# LF_v5_SensorBoard.net
KiCad netlist of a schematic drawn in Altium Designer
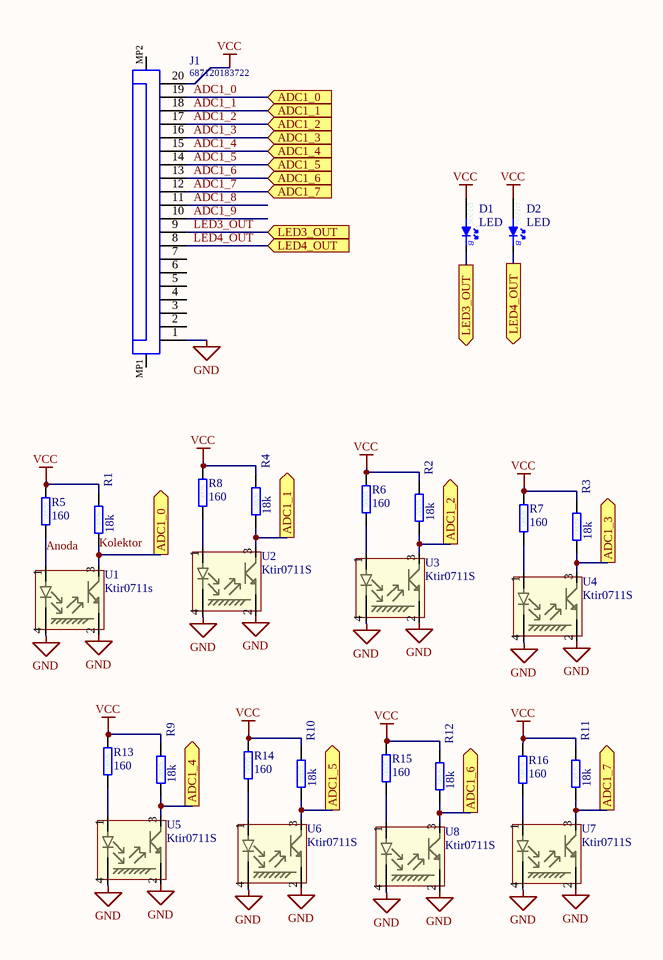
[diagram p0: LF_v5_SensorBoard.SchDoc]

(export (version "E")
  (design (tool "Eeschema 10.0.6"))
  (components
    (comp (ref "D1")
      (value "LED")
      (footprint "D1206_2")
      (description "Dioda LED Niebieska  120°   20mA   14-22 mCd")
      (libsource (lib "DIODY_LED_SMD__00001") (part "LL-S150BC-B4-1B  D1206"))
    )
    (comp (ref "D2")
      (value "LED")
      (footprint "D1206_2")
      (description "Dioda LED Niebieska  120°   20mA   14-22 mCd")
      (libsource (lib "DIODY_LED_SMD__00001") (part "LL-S150BC-B4-1B  D1206"))
    )
    (comp (ref "J1")
      (value "687120183722")
      (footprint "687120183722")
      (description "SMT ZIF Connectors Low Profile WR-FPC, Horizontal, Bottom Contact, pitch 0.5 mm, 20 pins")
      (fields (field (name "MANUFACTURER") "Wurth Elektronik") (field (name "PUBLISHER") "WurthElektronik"))
      (libsource (lib "Altium Content Vault") (part "WE-68X1201XXX22-20"))
    )
    (comp (ref "R1")
      (value "18k")
      (footprint "0805R")
      (description "Rezystor 0,125W")
      (libsource (lib "REZYSTORY_0805__00001") (part "160k-1%  0805"))
    )
    (comp (ref "R2")
      (value "18k")
      (footprint "0805R")
      (description "Rezystor 0,125W")
      (libsource (lib "REZYSTORY_0805__00001") (part "160k-1%  0805"))
    )
    (comp (ref "R3")
      (value "18k")
      (footprint "0805R")
      (description "Rezystor 0,125W")
      (libsource (lib "REZYSTORY_0805__00001") (part "160k-1%  0805"))
    )
    (comp (ref "R4")
      (value "18k")
      (footprint "0805R")
      (description "Rezystor 0,125W")
      (libsource (lib "REZYSTORY_0805__00001") (part "160k-1%  0805"))
    )
    (comp (ref "R5")
      (value "160")
      (footprint "0805R")
      (description "Rezystor 0,125W")
      (libsource (lib "REZYSTORY_0805__00001") (part "1k-1%  0805"))
    )
    (comp (ref "R6")
      (value "160")
      (footprint "0805R")
      (description "Rezystor 0,125W")
      (libsource (lib "REZYSTORY_0805__00001") (part "1k-1%  0805"))
    )
    (comp (ref "R7")
      (value "160")
      (footprint "0805R")
      (description "Rezystor 0,125W")
      (libsource (lib "REZYSTORY_0805__00001") (part "1k-1%  0805"))
    )
    (comp (ref "R8")
      (value "160")
      (footprint "0805R")
      (description "Rezystor 0,125W")
      (libsource (lib "REZYSTORY_0805__00001") (part "1k-1%  0805"))
    )
    (comp (ref "R9")
      (value "18k")
      (footprint "0805R")
      (description "Rezystor 0,125W")
      (libsource (lib "REZYSTORY_0805__00001") (part "160k-1%  0805"))
    )
    (comp (ref "R10")
      (value "18k")
      (footprint "0805R")
      (description "Rezystor 0,125W")
      (libsource (lib "REZYSTORY_0805__00001") (part "160k-1%  0805"))
    )
    (comp (ref "R11")
      (value "18k")
      (footprint "0805R")
      (description "Rezystor 0,125W")
      (libsource (lib "REZYSTORY_0805__00001") (part "160k-1%  0805"))
    )
    (comp (ref "R12")
      (value "18k")
      (footprint "0805R")
      (description "Rezystor 0,125W")
      (libsource (lib "REZYSTORY_0805__00001") (part "160k-1%  0805"))
    )
    (comp (ref "R13")
      (value "160")
      (footprint "0805R")
      (description "Rezystor 0,125W")
      (libsource (lib "REZYSTORY_0805__00001") (part "1k-1%  0805"))
    )
    (comp (ref "R14")
      (value "160")
      (footprint "0805R")
      (description "Rezystor 0,125W")
      (libsource (lib "REZYSTORY_0805__00001") (part "1k-1%  0805"))
    )
    (comp (ref "R15")
      (value "160")
      (footprint "0805R")
      (description "Rezystor 0,125W")
      (libsource (lib "REZYSTORY_0805__00001") (part "1k-1%  0805"))
    )
    (comp (ref "R16")
      (value "160")
      (footprint "0805R")
      (description "Rezystor 0,125W")
      (libsource (lib "REZYSTORY_0805__00001") (part "1k-1%  0805"))
    )
    (comp (ref "U1")
      (value "Ktir0711s")
      (footprint "KTIR0711S_fp")
      (libsource (lib "TEOR_Libki") (part "Component_1"))
    )
    (comp (ref "U2")
      (value "Ktir0711S")
      (footprint "KTIR0711S_fp")
      (libsource (lib "TEOR_Libki") (part "Component_1"))
    )
    (comp (ref "U3")
      (value "Ktir0711S")
      (footprint "KTIR0711S_fp")
      (libsource (lib "TEOR_Libki") (part "Component_1"))
    )
    (comp (ref "U4")
      (value "Ktir0711S")
      (footprint "KTIR0711S_fp")
      (libsource (lib "TEOR_Libki") (part "Component_1"))
    )
    (comp (ref "U5")
      (value "Ktir0711S")
      (footprint "KTIR0711S_fp")
      (libsource (lib "TEOR_Libki") (part "Component_1"))
    )
    (comp (ref "U6")
      (value "Ktir0711S")
      (footprint "KTIR0711S_fp")
      (libsource (lib "TEOR_Libki") (part "Component_1"))
    )
    (comp (ref "U7")
      (value "Ktir0711S")
      (footprint "KTIR0711S_fp")
      (libsource (lib "TEOR_Libki") (part "Component_1"))
    )
    (comp (ref "U8")
      (value "Ktir0711S")
      (footprint "KTIR0711S_fp")
      (libsource (lib "TEOR_Libki") (part "Component_1"))
    )
  )
  (nets
    (net (code "1") (name "/ADC1_0") (class "Default")
      (node (ref "J1") (pin "19") (pinfunction "19_19") (pintype "passive"))
      (node (ref "R1") (pin "2") (pintype "passive"))
      (node (ref "U1") (pin "3") (pinfunction "20_3") (pintype "passive"))
    )
    (net (code "2") (name "/ADC1_1") (class "Default")
      (node (ref "J1") (pin "18") (pinfunction "18_18") (pintype "passive"))
      (node (ref "R4") (pin "2") (pintype "passive"))
      (node (ref "U2") (pin "3") (pinfunction "20_3") (pintype "passive"))
    )
    (net (code "3") (name "/ADC1_2") (class "Default")
      (node (ref "J1") (pin "17") (pinfunction "17_17") (pintype "passive"))
      (node (ref "R2") (pin "2") (pintype "passive"))
      (node (ref "U3") (pin "3") (pinfunction "20_3") (pintype "passive"))
    )
    (net (code "4") (name "/ADC1_3") (class "Default")
      (node (ref "J1") (pin "16") (pinfunction "16_16") (pintype "passive"))
      (node (ref "R3") (pin "2") (pintype "passive"))
      (node (ref "U4") (pin "3") (pinfunction "20_3") (pintype "passive"))
    )
    (net (code "5") (name "/ADC1_4") (class "Default")
      (node (ref "J1") (pin "15") (pinfunction "15_15") (pintype "passive"))
      (node (ref "R9") (pin "2") (pintype "passive"))
      (node (ref "U5") (pin "3") (pinfunction "20_3") (pintype "passive"))
    )
    (net (code "6") (name "/ADC1_5") (class "Default")
      (node (ref "J1") (pin "14") (pinfunction "14_14") (pintype "passive"))
      (node (ref "R10") (pin "2") (pintype "passive"))
      (node (ref "U6") (pin "3") (pinfunction "20_3") (pintype "passive"))
    )
    (net (code "7") (name "/ADC1_6") (class "Default")
      (node (ref "J1") (pin "13") (pinfunction "13_13") (pintype "passive"))
      (node (ref "R12") (pin "2") (pintype "passive"))
      (node (ref "U8") (pin "3") (pinfunction "20_3") (pintype "passive"))
    )
    (net (code "8") (name "/ADC1_7") (class "Default")
      (node (ref "J1") (pin "12") (pinfunction "12_12") (pintype "passive"))
      (node (ref "R11") (pin "2") (pintype "passive"))
      (node (ref "U7") (pin "3") (pinfunction "20_3") (pintype "passive"))
    )
    (net (code "9") (name "/ADC1_8") (class "Default")
      (node (ref "J1") (pin "11") (pinfunction "11_11") (pintype "passive"))
    )
    (net (code "10") (name "/ADC1_9") (class "Default")
      (node (ref "J1") (pin "10") (pinfunction "10_10") (pintype "passive"))
    )
    (net (code "11") (name "/Anoda") (class "Default")
      (node (ref "R5") (pin "2") (pintype "passive"))
      (node (ref "U1") (pin "1") (pinfunction "19_1") (pintype "passive"))
    )
    (net (code "12") (name "/LED3_OUT") (class "Default")
      (node (ref "D1") (pin "1") (pinfunction "K_1") (pintype "passive"))
      (node (ref "J1") (pin "9") (pinfunction "9_9") (pintype "passive"))
    )
    (net (code "13") (name "/LED4_OUT") (class "Default")
      (node (ref "D2") (pin "1") (pinfunction "K_1") (pintype "passive"))
      (node (ref "J1") (pin "8") (pinfunction "8_8") (pintype "passive"))
    )
    (net (code "14") (name "GND") (class "Default")
      (node (ref "J1") (pin "1") (pinfunction "1_1") (pintype "passive"))
      (node (ref "U1") (pin "2") (pinfunction "22_2") (pintype "passive"))
      (node (ref "U1") (pin "4") (pinfunction "21_4") (pintype "passive"))
      (node (ref "U2") (pin "2") (pinfunction "22_2") (pintype "passive"))
      (node (ref "U2") (pin "4") (pinfunction "21_4") (pintype "passive"))
      (node (ref "U3") (pin "2") (pinfunction "22_2") (pintype "passive"))
      (node (ref "U3") (pin "4") (pinfunction "21_4") (pintype "passive"))
      (node (ref "U4") (pin "2") (pinfunction "22_2") (pintype "passive"))
      (node (ref "U4") (pin "4") (pinfunction "21_4") (pintype "passive"))
      (node (ref "U5") (pin "2") (pinfunction "22_2") (pintype "passive"))
      (node (ref "U5") (pin "4") (pinfunction "21_4") (pintype "passive"))
      (node (ref "U6") (pin "2") (pinfunction "22_2") (pintype "passive"))
      (node (ref "U6") (pin "4") (pinfunction "21_4") (pintype "passive"))
      (node (ref "U7") (pin "2") (pinfunction "22_2") (pintype "passive"))
      (node (ref "U7") (pin "4") (pinfunction "21_4") (pintype "passive"))
      (node (ref "U8") (pin "2") (pinfunction "22_2") (pintype "passive"))
      (node (ref "U8") (pin "4") (pinfunction "21_4") (pintype "passive"))
    )
    (net (code "15") (name "Net-(U2-19)") (class "Default")
      (node (ref "R8") (pin "2") (pintype "passive"))
      (node (ref "U2") (pin "1") (pinfunction "19_1") (pintype "passive"))
    )
    (net (code "16") (name "Net-(U3-19)") (class "Default")
      (node (ref "R6") (pin "2") (pintype "passive"))
      (node (ref "U3") (pin "1") (pinfunction "19_1") (pintype "passive"))
    )
    (net (code "17") (name "Net-(U4-19)") (class "Default")
      (node (ref "R7") (pin "2") (pintype "passive"))
      (node (ref "U4") (pin "1") (pinfunction "19_1") (pintype "passive"))
    )
    (net (code "18") (name "Net-(U5-19)") (class "Default")
      (node (ref "R13") (pin "2") (pintype "passive"))
      (node (ref "U5") (pin "1") (pinfunction "19_1") (pintype "passive"))
    )
    (net (code "19") (name "Net-(U6-19)") (class "Default")
      (node (ref "R14") (pin "2") (pintype "passive"))
      (node (ref "U6") (pin "1") (pinfunction "19_1") (pintype "passive"))
    )
    (net (code "20") (name "Net-(U7-19)") (class "Default")
      (node (ref "R16") (pin "2") (pintype "passive"))
      (node (ref "U7") (pin "1") (pinfunction "19_1") (pintype "passive"))
    )
    (net (code "21") (name "Net-(U8-19)") (class "Default")
      (node (ref "R15") (pin "2") (pintype "passive"))
      (node (ref "U8") (pin "1") (pinfunction "19_1") (pintype "passive"))
    )
    (net (code "22") (name "VCC") (class "Default")
      (node (ref "D1") (pin "2") (pinfunction "A_2") (pintype "passive"))
      (node (ref "D2") (pin "2") (pinfunction "A_2") (pintype "passive"))
      (node (ref "J1") (pin "20") (pinfunction "20_20") (pintype "passive"))
      (node (ref "R1") (pin "1") (pintype "passive"))
      (node (ref "R10") (pin "1") (pintype "passive"))
      (node (ref "R11") (pin "1") (pintype "passive"))
      (node (ref "R12") (pin "1") (pintype "passive"))
      (node (ref "R13") (pin "1") (pintype "passive"))
      (node (ref "R14") (pin "1") (pintype "passive"))
      (node (ref "R15") (pin "1") (pintype "passive"))
      (node (ref "R16") (pin "1") (pintype "passive"))
      (node (ref "R2") (pin "1") (pintype "passive"))
      (node (ref "R3") (pin "1") (pintype "passive"))
      (node (ref "R4") (pin "1") (pintype "passive"))
      (node (ref "R5") (pin "1") (pintype "passive"))
      (node (ref "R6") (pin "1") (pintype "passive"))
      (node (ref "R7") (pin "1") (pintype "passive"))
      (node (ref "R8") (pin "1") (pintype "passive"))
      (node (ref "R9") (pin "1") (pintype "passive"))
    )
    (net (code "23") (name "unconnected-(J1-Pad2)") (class "Default")
      (node (ref "J1") (pin "2") (pinfunction "2_2") (pintype "passive"))
    )
    (net (code "24") (name "unconnected-(J1-Pad3)") (class "Default")
      (node (ref "J1") (pin "3") (pinfunction "3_3") (pintype "passive"))
    )
    (net (code "25") (name "unconnected-(J1-Pad4)") (class "Default")
      (node (ref "J1") (pin "4") (pinfunction "4_4") (pintype "passive"))
    )
    (net (code "26") (name "unconnected-(J1-Pad5)") (class "Default")
      (node (ref "J1") (pin "5") (pinfunction "5_5") (pintype "passive"))
    )
    (net (code "27") (name "unconnected-(J1-Pad6)") (class "Default")
      (node (ref "J1") (pin "6") (pinfunction "6_6") (pintype "passive"))
    )
    (net (code "28") (name "unconnected-(J1-Pad7)") (class "Default")
      (node (ref "J1") (pin "7") (pinfunction "7_7") (pintype "passive"))
    )
    (net (code "29") (name "unconnected-(J1-PadMP1)") (class "Default")
      (node (ref "J1") (pin "MP1") (pinfunction "MP1_MP1") (pintype "passive"))
    )
    (net (code "30") (name "unconnected-(J1-PadMP2)") (class "Default")
      (node (ref "J1") (pin "MP2") (pinfunction "MP2_MP2") (pintype "passive"))
    )
  )
)
